# qi_adapter.net
KiCad netlist of a schematic drawn in Altium Designer
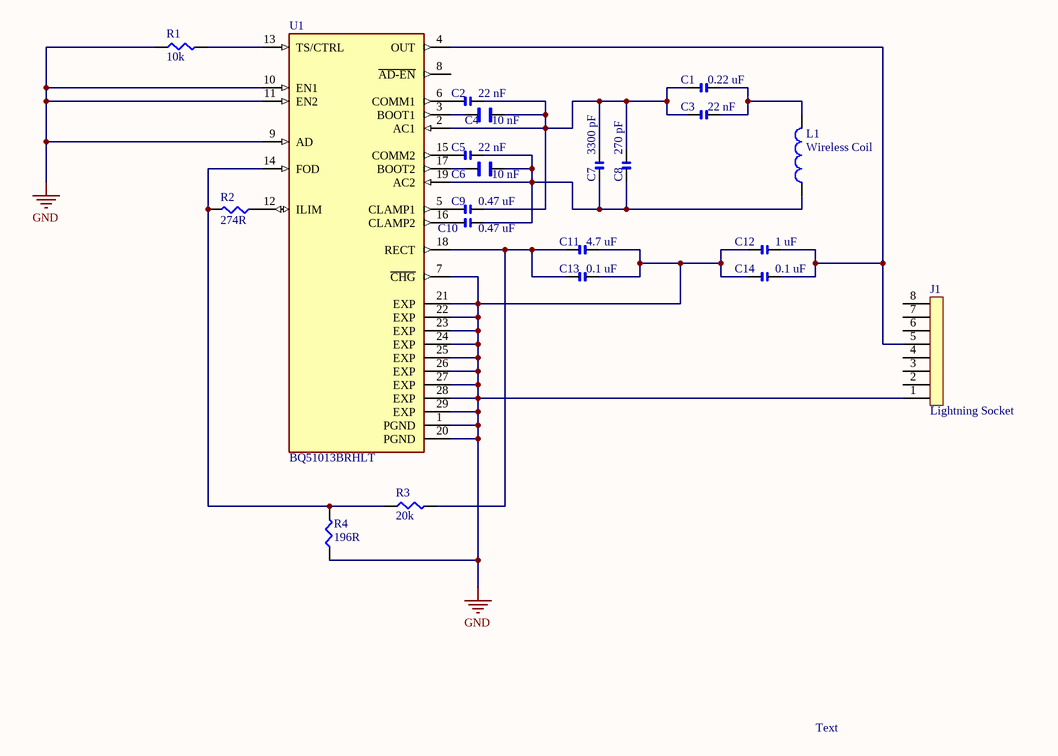
[diagram p0: qi_adapter.SchDoc]

(export (version "E")
  (design (tool "Eeschema 10.0.6"))
  (components
    (comp (ref "C1")
      (value "0.22 uF")
      (footprint "SMD-0402-CAP")
      (description "0.22µF ±10% 25V Ceramic Capacitor X5R 0402")
      (fields (field (name "DIGIKEY PART") "490-12265-1-ND") (field (name "MF") "Murata Electronics"))
      (libsource (lib "Qi Adapter Components") (part "0.22 uF 0402"))
    )
    (comp (ref "C2")
      (value "22 nF")
      (footprint "SMD-0402-CAP")
      (description "0.022µF -20%, +80% 25V Ceramic Capacitor Y5V (F) 0402")
      (fields (field (name "DIGIKEY PART") "311-3823-1-ND") (field (name "MF") "Yageo"))
      (libsource (lib "Qi Adapter Components") (part "22nF 0402"))
    )
    (comp (ref "C3")
      (value "22 nF")
      (footprint "SMD-0402-CAP")
      (description "0.022µF -20%, +80% 25V Ceramic Capacitor Y5V (F) 0402")
      (fields (field (name "DIGIKEY PART") "311-3823-1-ND") (field (name "MF") "Yageo"))
      (libsource (lib "Qi Adapter Components") (part "22nF 0402"))
    )
    (comp (ref "C4")
      (value "10 nF")
      (footprint "SMD-0402-CAP")
      (description "10000pF ±10% 25V Ceramic Capacitor X7R 0402")
      (fields (field (name "DIGIKEY PART") "399-1278-1-ND") (field (name "MF") "KEMET"))
      (libsource (lib "Qi Adapter Components") (part "10nF 0402"))
    )
    (comp (ref "C5")
      (value "22 nF")
      (footprint "SMD-0402-CAP")
      (description "0.022µF -20%, +80% 25V Ceramic Capacitor Y5V (F) 0402")
      (fields (field (name "DIGIKEY PART") "311-3823-1-ND") (field (name "MF") "Yageo"))
      (libsource (lib "Qi Adapter Components") (part "22nF 0402"))
    )
    (comp (ref "C6")
      (value "10 nF")
      (footprint "SMD-0402-CAP")
      (description "10000pF ±10% 25V Ceramic Capacitor X7R 0402")
      (fields (field (name "DIGIKEY PART") "399-1278-1-ND") (field (name "MF") "KEMET"))
      (libsource (lib "Qi Adapter Components") (part "10nF 0402"))
    )
    (comp (ref "C7")
      (value "3300 pF")
      (footprint "SMD-0402-CAP")
      (description "3300pF ±10% 25V Ceramic Capacitor X7R 0402")
      (fields (field (name "DIGIKEY PART") "732-7542-1-ND") (field (name "MF") "Würth Elektronik"))
      (libsource (lib "Qi Adapter Components") (part "3300 pF 0402"))
    )
    (comp (ref "C8")
      (value "270 pF")
      (footprint "SMD-0402-CAP")
      (description "270pF ±5% 25V Ceramic Capacitor C0G, NP0 040")
      (fields (field (name "DIGIKEY PART") "399-15315-1-ND") (field (name "MF") "KEMET"))
      (libsource (lib "Qi Adapter Components") (part "270 pF 0402"))
    )
    (comp (ref "C9")
      (value "0.47 uF")
      (footprint "SMD-0402-CAP")
      (description "0.47µF ±10% 25V Ceramic Capacitor X5R 0402")
      (fields (field (name "DIGIKEY PART") "490-12269-1-ND") (field (name "MF") "Murata Electronics"))
      (libsource (lib "Qi Adapter Components") (part "0.47uF 0402"))
    )
    (comp (ref "C10")
      (value "0.47 uF")
      (footprint "SMD-0402-CAP")
      (description "0.47µF ±10% 25V Ceramic Capacitor X5R 0402")
      (fields (field (name "DIGIKEY PART") "490-12269-1-ND") (field (name "MF") "Murata Electronics"))
      (libsource (lib "Qi Adapter Components") (part "0.47uF 0402"))
    )
    (comp (ref "C11")
      (value "4.7 uF")
      (footprint "SMD-0402-CAP")
      (description "4.7µF ±20% 16V Ceramic Capacitor X5R 0402")
      (fields (field (name "DIGIKEY PART") "478-10788-1-ND") (field (name "MF") "AVX Corporation"))
      (libsource (lib "Qi Adapter Components") (part "4.7uF 0402"))
    )
    (comp (ref "C12")
      (value "1 uF")
      (footprint "SMD-0402-CAP")
      (description "1µF ±10% 16V Ceramic Capacitor X5R 0402")
      (fields (field (name "DIGIKEY PART") "1276-1067-1-ND") (field (name "MF") "Samsung Electro-Mechanics"))
      (libsource (lib "Qi Adapter Components") (part "1uF 0402"))
    )
    (comp (ref "C13")
      (value "0.1 uF")
      (footprint "SMD-0402-CAP")
      (description "0.1µF -20%, +80% 16V Ceramic Capacitor Y5V (F) 0402")
      (fields (field (name "DIGIKEY PART") "1276-1004-1-ND") (field (name "MF") "Samsung Electro-Mechanics"))
      (libsource (lib "Qi Adapter Components") (part "0.1uF 0402"))
    )
    (comp (ref "C14")
      (value "0.1 uF")
      (footprint "SMD-0402-CAP")
      (description "0.1µF -20%, +80% 16V Ceramic Capacitor Y5V (F) 0402")
      (fields (field (name "DIGIKEY PART") "1276-1004-1-ND") (field (name "MF") "Samsung Electro-Mechanics"))
      (libsource (lib "Qi Adapter Components") (part "0.1uF 0402"))
    )
    (comp (ref "J1")
      (value "Lightning Socket")
      (footprint "Lightning Connector")
      (description "Female Lightning Socket")
      (libsource (lib "Qi Adapter Components") (part "Lightning Socket"))
    )
    (comp (ref "L1")
      (value "Wireless Coil")
      (footprint "Qi Coil")
      (description "Qi Compatible Wireless Receiver Coil")
      (libsource (lib "Qi Adapter Components") (part "Wireless Coil"))
    )
    (comp (ref "R1")
      (value "10k")
      (footprint "SMD-0402-RES")
      (description "10 kOhms ±5% 0.063W, 1/16W Chip Resistor 0402 Moisture Resistant Thick Film")
      (fields
        (field (name "PART NUMBER") "RC0402JR-0710KL")
        (field (name "DIGI-KEY PART NUMBER") "311-10KJRCT-ND")
      )
      (libsource (lib "Qi Adapter Components") (part "10K 0402"))
    )
    (comp (ref "R2")
      (value "274R")
      (footprint "SMD-0402-RES")
      (description "274 Ohms ±1% 0.1W, 1/10W Chip Resistor 0402")
      (fields (field (name "PART NUMBER") "ERJ-2RKF2740X") (field (name "DIGI-KEY PART NUMBER") "P274LCT-ND"))
      (libsource (lib "Qi Adapter Components") (part "274R 0402"))
    )
    (comp (ref "R3")
      (value "20k")
      (footprint "SMD-0402-RES")
      (description "20 kOhms ±1% 0.1W, 1/10W Chip Resistor 0402")
      (fields
        (field (name "PART NUMBER") "ERJ-2RKF2002X")
        (field (name "DIGI-KEY PART NUMBER") "P20.0KLCT-ND")
      )
      (libsource (lib "Qi Adapter Components") (part "20K 0402"))
    )
    (comp (ref "R4")
      (value "196R")
      (footprint "SMD-0402-RES")
      (description "196 Ohms ±1% 0.1W, 1/10W Chip Resistor 0402")
      (fields (field (name "PART NUMBER") "ERJ-2RKF1960X") (field (name "DIGI-KEY PART NUMBER") "P196LCT-ND"))
      (libsource (lib "Qi Adapter Components") (part "196R 0402"))
    )
    (comp (ref "U1")
      (value "BQ51013BRHLT")
      (footprint "IC_BQ51013BRHLT")
      (description "Wireless Power Receiver PMIC 20-VQFN _3.5x4.5_")
      (fields (field (name "MF") "Texas Instruments") (field (name "DIGI-KEY_PART_NUMBER") "296-35638-1-ND"))
      (libsource (lib "Qi Adapter Components") (part "BQ51013BRHLT"))
    )
  )
  (nets
    (net (code "1") (name "GND") (class "Default")
      (node (ref "C11") (pin "1") (pinfunction "1_1") (pintype "passive"))
      (node (ref "C12") (pin "2") (pinfunction "2_2") (pintype "passive"))
      (node (ref "C13") (pin "1") (pinfunction "1_1") (pintype "passive"))
      (node (ref "C14") (pin "2") (pinfunction "2_2") (pintype "passive"))
      (node (ref "J1") (pin "1") (pinfunction "GND_1") (pintype "passive"))
      (node (ref "R1") (pin "1") (pinfunction "1_1") (pintype "passive"))
      (node (ref "R4") (pin "2") (pinfunction "2_2") (pintype "passive"))
      (node (ref "U1") (pin "1") (pinfunction "PGND_1") (pintype "power_in"))
      (node (ref "U1") (pin "10") (pinfunction "EN1_10") (pintype "input"))
      (node (ref "U1") (pin "11") (pinfunction "EN2_11") (pintype "input"))
      (node (ref "U1") (pin "20") (pinfunction "PGND_20") (pintype "power_in"))
      (node (ref "U1") (pin "21") (pinfunction "EXP_21") (pintype "passive"))
      (node (ref "U1") (pin "22") (pinfunction "EXP_22") (pintype "passive"))
      (node (ref "U1") (pin "23") (pinfunction "EXP_23") (pintype "passive"))
      (node (ref "U1") (pin "24") (pinfunction "EXP_24") (pintype "passive"))
      (node (ref "U1") (pin "25") (pinfunction "EXP_25") (pintype "passive"))
      (node (ref "U1") (pin "26") (pinfunction "EXP_26") (pintype "passive"))
      (node (ref "U1") (pin "27") (pinfunction "EXP_27") (pintype "passive"))
      (node (ref "U1") (pin "28") (pinfunction "EXP_28") (pintype "passive"))
      (node (ref "U1") (pin "29") (pinfunction "EXP_29") (pintype "passive"))
      (node (ref "U1") (pin "7") (pinfunction "~{CHG}_7") (pintype "output"))
      (node (ref "U1") (pin "9") (pinfunction "AD_9") (pintype "input"))
    )
    (net (code "2") (name "Net-(C1-Pad1)") (class "Default")
      (node (ref "C1") (pin "1") (pinfunction "1_1") (pintype "passive"))
      (node (ref "C3") (pin "1") (pinfunction "1_1") (pintype "passive"))
      (node (ref "L1") (pin "1") (pinfunction "1_1") (pintype "passive"))
    )
    (net (code "3") (name "Net-(J1-Vcc)") (class "Default")
      (node (ref "C12") (pin "1") (pinfunction "1_1") (pintype "passive"))
      (node (ref "C14") (pin "1") (pinfunction "1_1") (pintype "passive"))
      (node (ref "J1") (pin "5") (pinfunction "Vcc_5") (pintype "passive"))
      (node (ref "U1") (pin "4") (pinfunction "OUT_4") (pintype "output"))
    )
    (net (code "4") (name "Net-(U1-AC1)") (class "Default")
      (node (ref "C1") (pin "2") (pinfunction "2_2") (pintype "passive"))
      (node (ref "C2") (pin "1") (pinfunction "1_1") (pintype "passive"))
      (node (ref "C3") (pin "2") (pinfunction "2_2") (pintype "passive"))
      (node (ref "C4") (pin "1") (pinfunction "1_1") (pintype "passive"))
      (node (ref "C7") (pin "1") (pinfunction "1_1") (pintype "passive"))
      (node (ref "C8") (pin "1") (pinfunction "1_1") (pintype "passive"))
      (node (ref "C9") (pin "1") (pinfunction "1_1") (pintype "passive"))
      (node (ref "U1") (pin "2") (pinfunction "AC1_2") (pintype "input"))
    )
    (net (code "5") (name "Net-(U1-AC2)") (class "Default")
      (node (ref "C10") (pin "1") (pinfunction "1_1") (pintype "passive"))
      (node (ref "C5") (pin "1") (pinfunction "1_1") (pintype "passive"))
      (node (ref "C6") (pin "1") (pinfunction "1_1") (pintype "passive"))
      (node (ref "C7") (pin "2") (pinfunction "2_2") (pintype "passive"))
      (node (ref "C8") (pin "2") (pinfunction "2_2") (pintype "passive"))
      (node (ref "L1") (pin "2") (pinfunction "2_2") (pintype "passive"))
      (node (ref "U1") (pin "19") (pinfunction "AC2_19") (pintype "input"))
    )
    (net (code "6") (name "Net-(U1-BOOT1)") (class "Default")
      (node (ref "C4") (pin "2") (pinfunction "2_2") (pintype "passive"))
      (node (ref "U1") (pin "3") (pinfunction "BOOT1_3") (pintype "output"))
    )
    (net (code "7") (name "Net-(U1-BOOT2)") (class "Default")
      (node (ref "C6") (pin "2") (pinfunction "2_2") (pintype "passive"))
      (node (ref "U1") (pin "17") (pinfunction "BOOT2_17") (pintype "output"))
    )
    (net (code "8") (name "Net-(U1-CLAMP1)") (class "Default")
      (node (ref "C9") (pin "2") (pinfunction "2_2") (pintype "passive"))
      (node (ref "U1") (pin "5") (pinfunction "CLAMP1_5") (pintype "output"))
    )
    (net (code "9") (name "Net-(U1-CLAMP2)") (class "Default")
      (node (ref "C10") (pin "2") (pinfunction "2_2") (pintype "passive"))
      (node (ref "U1") (pin "16") (pinfunction "CLAMP2_16") (pintype "output"))
    )
    (net (code "10") (name "Net-(U1-COMM1)") (class "Default")
      (node (ref "C2") (pin "2") (pinfunction "2_2") (pintype "passive"))
      (node (ref "U1") (pin "6") (pinfunction "COMM1_6") (pintype "output"))
    )
    (net (code "11") (name "Net-(U1-COMM2)") (class "Default")
      (node (ref "C5") (pin "2") (pinfunction "2_2") (pintype "passive"))
      (node (ref "U1") (pin "15") (pinfunction "COMM2_15") (pintype "output"))
    )
    (net (code "12") (name "Net-(U1-FOD)") (class "Default")
      (node (ref "R2") (pin "2") (pinfunction "2_2") (pintype "passive"))
      (node (ref "R3") (pin "1") (pinfunction "1_1") (pintype "passive"))
      (node (ref "R4") (pin "1") (pinfunction "1_1") (pintype "passive"))
      (node (ref "U1") (pin "14") (pinfunction "FOD_14") (pintype "input"))
    )
    (net (code "13") (name "Net-(U1-ILIM)") (class "Default")
      (node (ref "R2") (pin "1") (pinfunction "1_1") (pintype "passive"))
      (node (ref "U1") (pin "12") (pinfunction "ILIM_12") (pintype "bidirectional"))
    )
    (net (code "14") (name "Net-(U1-RECT)") (class "Default")
      (node (ref "C11") (pin "2") (pinfunction "2_2") (pintype "passive"))
      (node (ref "C13") (pin "2") (pinfunction "2_2") (pintype "passive"))
      (node (ref "R3") (pin "2") (pinfunction "2_2") (pintype "passive"))
      (node (ref "U1") (pin "18") (pinfunction "RECT_18") (pintype "output"))
    )
    (net (code "15") (name "Net-(U1-TS{slash}CTRL)") (class "Default")
      (node (ref "R1") (pin "2") (pinfunction "2_2") (pintype "passive"))
      (node (ref "U1") (pin "13") (pinfunction "TS/CTRL_13") (pintype "input"))
    )
    (net (code "16") (name "unconnected-(J1-ID0-Pad4)") (class "Default")
      (node (ref "J1") (pin "4") (pinfunction "ID0_4") (pintype "passive"))
    )
    (net (code "17") (name "unconnected-(J1-ID1-Pad8)") (class "Default")
      (node (ref "J1") (pin "8") (pinfunction "ID1_8") (pintype "passive"))
    )
    (net (code "18") (name "unconnected-(J1-L0+-Pad2)") (class "Default")
      (node (ref "J1") (pin "2") (pinfunction "L0+_2") (pintype "passive"))
    )
    (net (code "19") (name "unconnected-(J1-L0--Pad3)") (class "Default")
      (node (ref "J1") (pin "3") (pinfunction "L0-_3") (pintype "passive"))
    )
    (net (code "20") (name "unconnected-(J1-L1+-Pad7)") (class "Default")
      (node (ref "J1") (pin "7") (pinfunction "L1+_7") (pintype "passive"))
    )
    (net (code "21") (name "unconnected-(J1-L1--Pad6)") (class "Default")
      (node (ref "J1") (pin "6") (pinfunction "L1-_6") (pintype "passive"))
    )
    (net (code "22") (name "unconnected-(U1-~{AD-EN}-Pad8)") (class "Default")
      (node (ref "U1") (pin "8") (pinfunction "~{AD-EN}_8") (pintype "output"))
    )
  )
)
